# DA_Finale_Version.net
KiCad netlist of a schematic drawn in EAGLE
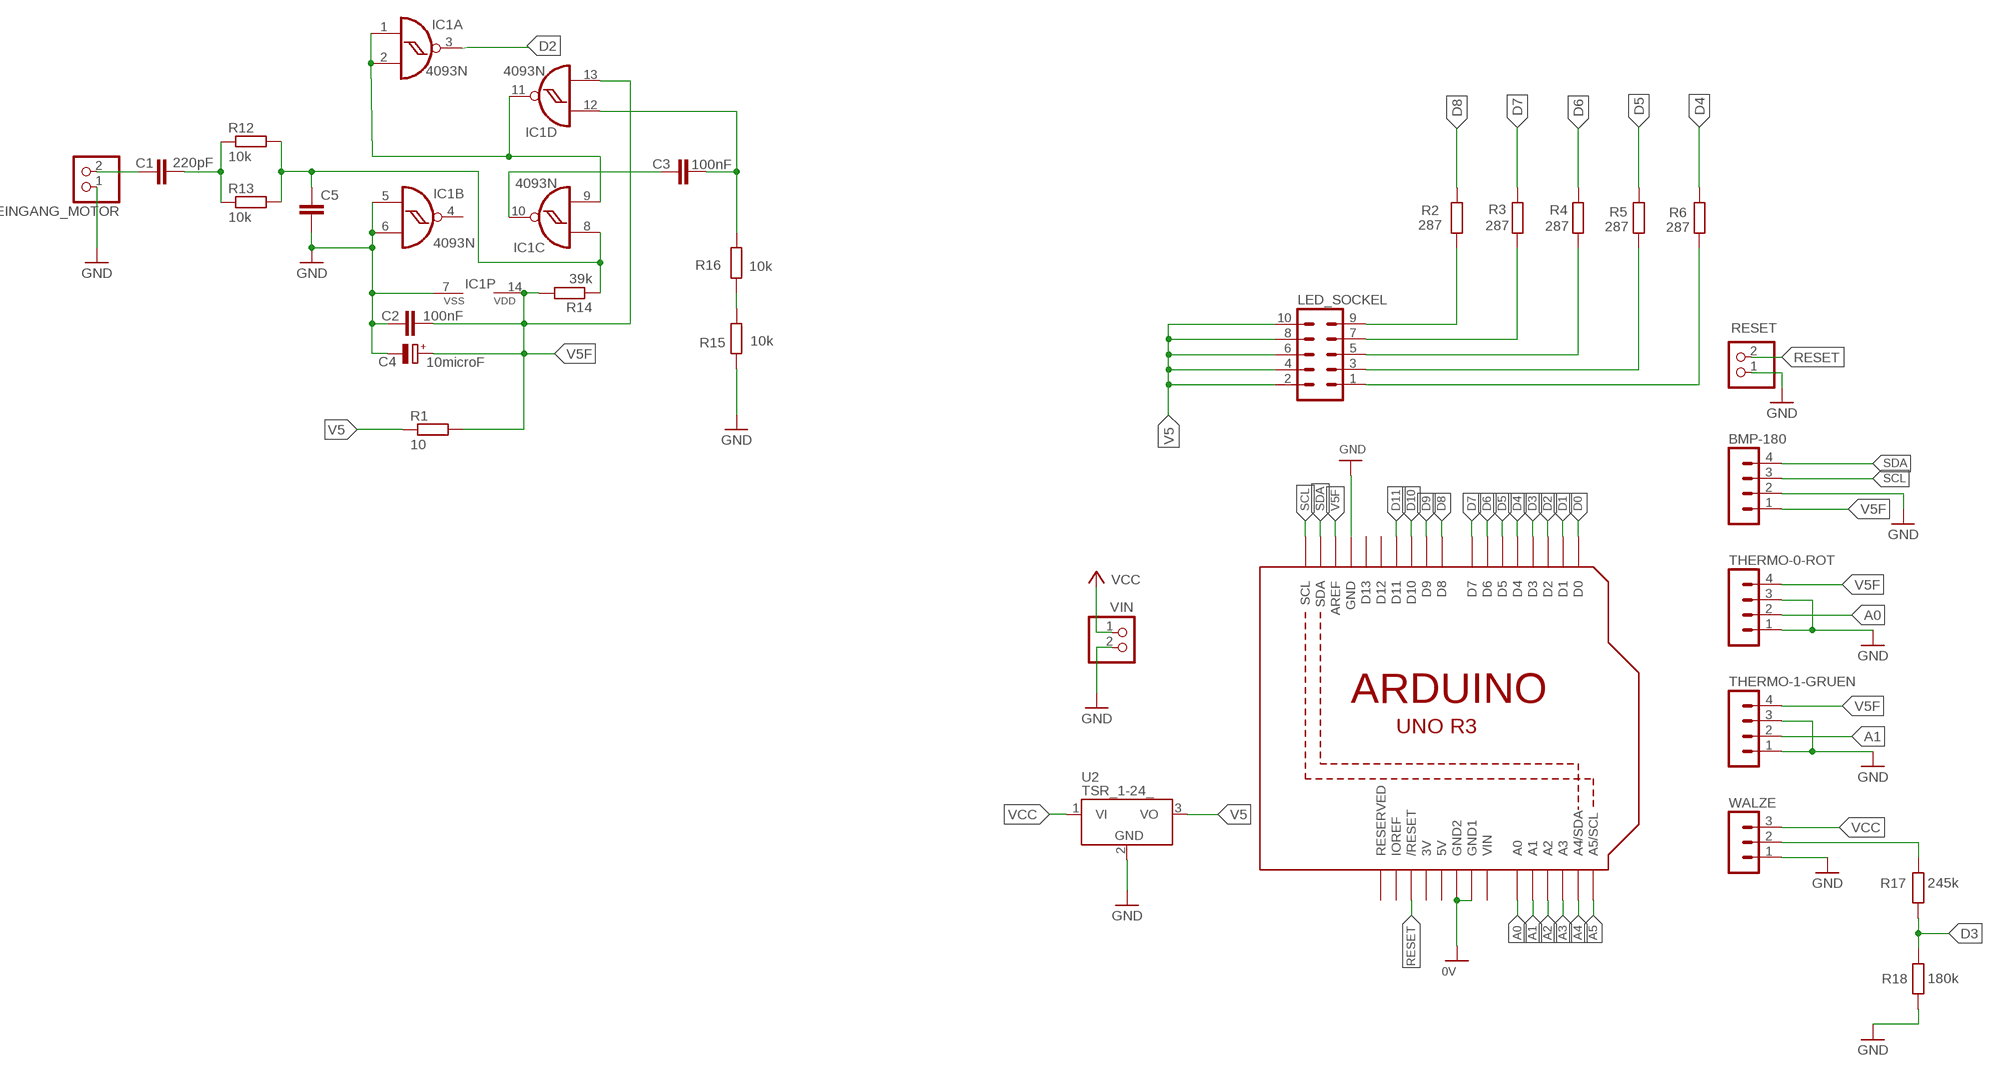
[diagram p0: schematic, sheet 1]

(export (version "E")
  (design (tool "Eeschema 10.0.6"))
  (components
    (comp (ref "BMP-180")
      (value "MA04-1")
      (footprint "eagle-import:MA04-1")
      (libsource (lib "eagle-import") (part "MA04-1"))
    )
    (comp (ref "C1")
      (value "220pF")
      (footprint "eagle-import:C050-025X075")
      (libsource (lib "eagle-import") (part "C-EU050-025X075"))
    )
    (comp (ref "C2")
      (value "100nF")
      (footprint "eagle-import:C050-025X075")
      (libsource (lib "eagle-import") (part "C-EU050-025X075"))
    )
    (comp (ref "C3")
      (value "100nF")
      (footprint "eagle-import:C050-025X075")
      (libsource (lib "eagle-import") (part "C-EU050-025X075"))
    )
    (comp (ref "C4")
      (value "10microF")
      (footprint "eagle-import:E3,5-8")
      (libsource (lib "eagle-import") (part "CPOL-EUE3.5-8"))
    )
    (comp (ref "C5")
      (value "C-EU050-025X075")
      (footprint "eagle-import:C050-025X075")
      (libsource (lib "eagle-import") (part "C-EU050-025X075"))
    )
    (comp (ref "EINGANG_MOTOR")
      (value "PINHD-1X2")
      (footprint "eagle-import:1X02")
      (libsource (lib "eagle-import") (part "PINHD-1X2"))
    )
    (comp (ref "IC1")
      (value "4093N")
      (footprint "eagle-import:DIL14")
      (libsource (lib "eagle-import") (part "4093N"))
    )
    (comp (ref "LED_SOCKEL")
      (value "MA05-2")
      (footprint "eagle-import:MA05-2")
      (libsource (lib "eagle-import") (part "MA05-2"))
    )
    (comp (ref "R1")
      (value "10")
      (footprint "eagle-import:0207_7")
      (libsource (lib "eagle-import") (part "R-EU_0207/7"))
    )
    (comp (ref "R2")
      (value "287")
      (footprint "eagle-import:0207_10")
      (libsource (lib "eagle-import") (part "R-EU_0207/10"))
    )
    (comp (ref "R3")
      (value "287")
      (footprint "eagle-import:0207_10")
      (libsource (lib "eagle-import") (part "R-EU_0207/10"))
    )
    (comp (ref "R4")
      (value "287")
      (footprint "eagle-import:0207_10")
      (libsource (lib "eagle-import") (part "R-EU_0207/10"))
    )
    (comp (ref "R5")
      (value "287")
      (footprint "eagle-import:0207_10")
      (libsource (lib "eagle-import") (part "R-EU_0207/10"))
    )
    (comp (ref "R6")
      (value "287")
      (footprint "eagle-import:0207_10")
      (libsource (lib "eagle-import") (part "R-EU_0207/10"))
    )
    (comp (ref "R12")
      (value "10k")
      (footprint "eagle-import:0207_7")
      (libsource (lib "eagle-import") (part "resistor_348_R-EU_0207/7"))
    )
    (comp (ref "R13")
      (value "10k")
      (footprint "eagle-import:0207_7")
      (libsource (lib "eagle-import") (part "resistor_348_R-EU_0207/7"))
    )
    (comp (ref "R14")
      (value "39k")
      (footprint "eagle-import:0207_7")
      (libsource (lib "eagle-import") (part "resistor_348_R-EU_0207/7"))
    )
    (comp (ref "R15")
      (value "10k")
      (footprint "eagle-import:0207_7")
      (libsource (lib "eagle-import") (part "resistor_348_R-EU_0207/7"))
    )
    (comp (ref "R16")
      (value "10k")
      (footprint "eagle-import:0207_7")
      (libsource (lib "eagle-import") (part "resistor_348_R-EU_0207/7"))
    )
    (comp (ref "R17")
      (value "245k")
      (footprint "eagle-import:0207_7")
      (libsource (lib "eagle-import") (part "resistor_348_R-EU_0207/7"))
    )
    (comp (ref "R18")
      (value "180k")
      (footprint "eagle-import:0207_7")
      (libsource (lib "eagle-import") (part "resistor_348_R-EU_0207/7"))
    )
    (comp (ref "RESET")
      (value "PINHD-1X2")
      (footprint "eagle-import:1X02")
      (libsource (lib "eagle-import") (part "PINHD-1X2"))
    )
    (comp (ref "THERMO-0-ROT")
      (value "MA04-1")
      (footprint "eagle-import:MA04-1")
      (libsource (lib "eagle-import") (part "MA04-1"))
    )
    (comp (ref "THERMO-1-GRUEN")
      (value "MA04-1")
      (footprint "eagle-import:MA04-1")
      (libsource (lib "eagle-import") (part "MA04-1"))
    )
    (comp (ref "U1")
      (value "ARDUINOR3-BPLACE")
      (footprint "eagle-import:ARDUINOR3-BPLACE")
      (libsource (lib "eagle-import") (part "ARDUINOR3-BPLACE"))
    )
    (comp (ref "U2")
      (value "TSR_1-24_")
      (footprint "eagle-import:TSR-1")
      (libsource (lib "eagle-import") (part "TSR_1-24_"))
    )
    (comp (ref "VIN")
      (value "PINHD-1X2")
      (footprint "eagle-import:1X02")
      (libsource (lib "eagle-import") (part "PINHD-1X2"))
    )
    (comp (ref "WALZE")
      (value "MA03-1")
      (footprint "eagle-import:MA03-1")
      (libsource (lib "eagle-import") (part "MA03-1"))
    )
  )
  (nets
    (net (code "1") (name "/3V") (class "Default")
      (node (ref "U1") (pin "3V") (pinfunction "3V_3V") (pintype "power_in"))
    )
    (net (code "2") (name "/5V") (class "Default")
      (node (ref "U1") (pin "5V") (pinfunction "5V_5V") (pintype "power_in"))
    )
    (net (code "3") (name "/VIN") (class "Default")
      (node (ref "U1") (pin "VIN") (pinfunction "VIN_VIN") (pintype "power_in"))
    )
    (net (code "4") (name "0V") (class "Default")
      (node (ref "BMP-180") (pin "2") (pinfunction "2_2") (pintype "passive"))
      (node (ref "C2") (pin "1") (pinfunction "1_1") (pintype "passive"))
      (node (ref "C4") (pin "-") (pinfunction "-_-") (pintype "passive"))
      (node (ref "C5") (pin "2") (pinfunction "2_2") (pintype "passive"))
      (node (ref "EINGANG_MOTOR") (pin "1") (pinfunction "1_1") (pintype "passive"))
      (node (ref "IC1") (pin "5") (pinfunction "I0_5") (pintype "input"))
      (node (ref "IC1") (pin "6") (pinfunction "I1_6") (pintype "input"))
      (node (ref "IC1") (pin "7") (pinfunction "VSS_7") (pintype "power_in"))
      (node (ref "R15") (pin "1") (pinfunction "1_1") (pintype "passive"))
      (node (ref "R18") (pin "1") (pinfunction "1_1") (pintype "passive"))
      (node (ref "RESET") (pin "1") (pinfunction "1_1") (pintype "passive"))
      (node (ref "THERMO-0-ROT") (pin "1") (pinfunction "1_1") (pintype "passive"))
      (node (ref "THERMO-0-ROT") (pin "3") (pinfunction "3_3") (pintype "passive"))
      (node (ref "THERMO-1-GRUEN") (pin "1") (pinfunction "1_1") (pintype "passive"))
      (node (ref "THERMO-1-GRUEN") (pin "3") (pinfunction "3_3") (pintype "passive"))
      (node (ref "U1") (pin "GND") (pinfunction "GND_GND") (pintype "power_in"))
      (node (ref "U1") (pin "GND1") (pinfunction "GND1_GND1") (pintype "power_in"))
      (node (ref "U1") (pin "GND2") (pinfunction "GND2_GND2") (pintype "power_in"))
      (node (ref "U2") (pin "2") (pinfunction "GND_2") (pintype "power_in"))
      (node (ref "VIN") (pin "2") (pinfunction "2_2") (pintype "passive"))
      (node (ref "WALZE") (pin "1") (pinfunction "1_1") (pintype "passive"))
    )
    (net (code "5") (name "A0") (class "Default")
      (node (ref "THERMO-0-ROT") (pin "2") (pinfunction "2_2") (pintype "passive"))
      (node (ref "U1") (pin "A0") (pinfunction "A0_A0") (pintype "bidirectional"))
    )
    (net (code "6") (name "A1") (class "Default")
      (node (ref "THERMO-1-GRUEN") (pin "2") (pinfunction "2_2") (pintype "passive"))
      (node (ref "U1") (pin "A1") (pinfunction "A1_A1") (pintype "bidirectional"))
    )
    (net (code "7") (name "A2") (class "Default")
      (node (ref "U1") (pin "A2") (pinfunction "A2_A2") (pintype "bidirectional"))
    )
    (net (code "8") (name "A3") (class "Default")
      (node (ref "U1") (pin "A3") (pinfunction "A3_A3") (pintype "bidirectional"))
    )
    (net (code "9") (name "A4") (class "Default")
      (node (ref "U1") (pin "A4") (pinfunction "A4/SDA_A4") (pintype "bidirectional"))
    )
    (net (code "10") (name "A5") (class "Default")
      (node (ref "U1") (pin "A5") (pinfunction "A5/SCL_A5") (pintype "bidirectional"))
    )
    (net (code "11") (name "D0") (class "Default")
      (node (ref "U1") (pin "D0") (pinfunction "D0_D0") (pintype "bidirectional"))
    )
    (net (code "12") (name "D1") (class "Default")
      (node (ref "U1") (pin "D1") (pinfunction "D1_D1") (pintype "bidirectional"))
    )
    (net (code "13") (name "D2") (class "Default")
      (node (ref "IC1") (pin "3") (pinfunction "O_3") (pintype "output"))
      (node (ref "U1") (pin "D2") (pinfunction "D2_D2") (pintype "bidirectional"))
    )
    (net (code "14") (name "D3") (class "Default")
      (node (ref "R17") (pin "1") (pinfunction "1_1") (pintype "passive"))
      (node (ref "R18") (pin "2") (pinfunction "2_2") (pintype "passive"))
      (node (ref "U1") (pin "D3") (pinfunction "D3_D3") (pintype "bidirectional"))
    )
    (net (code "15") (name "D4") (class "Default")
      (node (ref "R6") (pin "2") (pinfunction "2_2") (pintype "passive"))
      (node (ref "U1") (pin "D4") (pinfunction "D4_D4") (pintype "bidirectional"))
    )
    (net (code "16") (name "D5") (class "Default")
      (node (ref "R5") (pin "2") (pinfunction "2_2") (pintype "passive"))
      (node (ref "U1") (pin "D5") (pinfunction "D5_D5") (pintype "bidirectional"))
    )
    (net (code "17") (name "D6") (class "Default")
      (node (ref "R4") (pin "2") (pinfunction "2_2") (pintype "passive"))
      (node (ref "U1") (pin "D6") (pinfunction "D6_D6") (pintype "bidirectional"))
    )
    (net (code "18") (name "D7") (class "Default")
      (node (ref "R3") (pin "2") (pinfunction "2_2") (pintype "passive"))
      (node (ref "U1") (pin "D7") (pinfunction "D7_D7") (pintype "bidirectional"))
    )
    (net (code "19") (name "D8") (class "Default")
      (node (ref "R2") (pin "2") (pinfunction "2_2") (pintype "passive"))
      (node (ref "U1") (pin "D8") (pinfunction "D8_D8") (pintype "bidirectional"))
    )
    (net (code "20") (name "D9") (class "Default")
      (node (ref "U1") (pin "D9") (pinfunction "D9_D9") (pintype "bidirectional"))
    )
    (net (code "21") (name "D10") (class "Default")
      (node (ref "U1") (pin "D10") (pinfunction "D10_D10") (pintype "bidirectional"))
    )
    (net (code "22") (name "D11") (class "Default")
      (node (ref "U1") (pin "D11") (pinfunction "D11_D11") (pintype "bidirectional"))
    )
    (net (code "23") (name "Net-(C1-Pad1)") (class "Default")
      (node (ref "C1") (pin "1") (pinfunction "1_1") (pintype "passive"))
      (node (ref "EINGANG_MOTOR") (pin "2") (pinfunction "2_2") (pintype "passive"))
    )
    (net (code "24") (name "Net-(C1-Pad2)") (class "Default")
      (node (ref "C1") (pin "2") (pinfunction "2_2") (pintype "passive"))
      (node (ref "R12") (pin "1") (pinfunction "1_1") (pintype "passive"))
      (node (ref "R13") (pin "1") (pinfunction "1_1") (pintype "passive"))
    )
    (net (code "25") (name "Net-(IC1A-I0)") (class "Default")
      (node (ref "IC1") (pin "1") (pinfunction "I0_1") (pintype "input"))
      (node (ref "IC1") (pin "11") (pinfunction "O_11") (pintype "output"))
      (node (ref "IC1") (pin "2") (pinfunction "I1_2") (pintype "input"))
      (node (ref "IC1") (pin "9") (pinfunction "I1_9") (pintype "input"))
    )
    (net (code "26") (name "Net-(IC1C-I0)") (class "Default")
      (node (ref "C5") (pin "1") (pinfunction "1_1") (pintype "passive"))
      (node (ref "IC1") (pin "8") (pinfunction "I0_8") (pintype "input"))
      (node (ref "R12") (pin "2") (pinfunction "2_2") (pintype "passive"))
      (node (ref "R13") (pin "2") (pinfunction "2_2") (pintype "passive"))
      (node (ref "R14") (pin "1") (pinfunction "1_1") (pintype "passive"))
    )
    (net (code "27") (name "Net-(IC1C-O)") (class "Default")
      (node (ref "C3") (pin "2") (pinfunction "2_2") (pintype "passive"))
      (node (ref "IC1") (pin "10") (pinfunction "O_10") (pintype "output"))
    )
    (net (code "28") (name "Net-(IC1D-I0)") (class "Default")
      (node (ref "C3") (pin "1") (pinfunction "1_1") (pintype "passive"))
      (node (ref "IC1") (pin "12") (pinfunction "I0_12") (pintype "input"))
      (node (ref "R16") (pin "2") (pinfunction "2_2") (pintype "passive"))
    )
    (net (code "29") (name "Net-(LED_SOCKEL-Pad1)") (class "Default")
      (node (ref "LED_SOCKEL") (pin "1") (pinfunction "1_1") (pintype "passive"))
      (node (ref "R6") (pin "1") (pinfunction "1_1") (pintype "passive"))
    )
    (net (code "30") (name "Net-(LED_SOCKEL-Pad3)") (class "Default")
      (node (ref "LED_SOCKEL") (pin "3") (pinfunction "3_3") (pintype "passive"))
      (node (ref "R5") (pin "1") (pinfunction "1_1") (pintype "passive"))
    )
    (net (code "31") (name "Net-(LED_SOCKEL-Pad5)") (class "Default")
      (node (ref "LED_SOCKEL") (pin "5") (pinfunction "5_5") (pintype "passive"))
      (node (ref "R4") (pin "1") (pinfunction "1_1") (pintype "passive"))
    )
    (net (code "32") (name "Net-(LED_SOCKEL-Pad7)") (class "Default")
      (node (ref "LED_SOCKEL") (pin "7") (pinfunction "7_7") (pintype "passive"))
      (node (ref "R3") (pin "1") (pinfunction "1_1") (pintype "passive"))
    )
    (net (code "33") (name "Net-(LED_SOCKEL-Pad9)") (class "Default")
      (node (ref "LED_SOCKEL") (pin "9") (pinfunction "9_9") (pintype "passive"))
      (node (ref "R2") (pin "1") (pinfunction "1_1") (pintype "passive"))
    )
    (net (code "34") (name "Net-(R15-Pad2)") (class "Default")
      (node (ref "R15") (pin "2") (pinfunction "2_2") (pintype "passive"))
      (node (ref "R16") (pin "1") (pinfunction "1_1") (pintype "passive"))
    )
    (net (code "35") (name "Net-(R17-Pad2)") (class "Default")
      (node (ref "R17") (pin "2") (pinfunction "2_2") (pintype "passive"))
      (node (ref "WALZE") (pin "2") (pinfunction "2_2") (pintype "passive"))
    )
    (net (code "36") (name "RESET") (class "Default")
      (node (ref "RESET") (pin "2") (pinfunction "2_2") (pintype "passive"))
      (node (ref "U1") (pin "RESET") (pinfunction "/RESET_RESET") (pintype "bidirectional"))
    )
    (net (code "37") (name "SCL") (class "Default")
      (node (ref "BMP-180") (pin "3") (pinfunction "3_3") (pintype "passive"))
      (node (ref "U1") (pin "SCL") (pinfunction "SCL_SCL") (pintype "bidirectional"))
    )
    (net (code "38") (name "SDA") (class "Default")
      (node (ref "BMP-180") (pin "4") (pinfunction "4_4") (pintype "passive"))
      (node (ref "U1") (pin "SDA") (pinfunction "SDA_SDA") (pintype "bidirectional"))
    )
    (net (code "39") (name "V5") (class "Default")
      (node (ref "LED_SOCKEL") (pin "10") (pinfunction "10_10") (pintype "passive"))
      (node (ref "LED_SOCKEL") (pin "2") (pinfunction "2_2") (pintype "passive"))
      (node (ref "LED_SOCKEL") (pin "4") (pinfunction "4_4") (pintype "passive"))
      (node (ref "LED_SOCKEL") (pin "6") (pinfunction "6_6") (pintype "passive"))
      (node (ref "LED_SOCKEL") (pin "8") (pinfunction "8_8") (pintype "passive"))
      (node (ref "R1") (pin "1") (pinfunction "1_1") (pintype "passive"))
      (node (ref "U2") (pin "3") (pinfunction "VO_3") (pintype "power_in"))
    )
    (net (code "40") (name "V5F") (class "Default")
      (node (ref "BMP-180") (pin "1") (pinfunction "1_1") (pintype "passive"))
      (node (ref "C2") (pin "2") (pinfunction "2_2") (pintype "passive"))
      (node (ref "C4") (pin "+") (pinfunction "+_+") (pintype "passive"))
      (node (ref "IC1") (pin "13") (pinfunction "I1_13") (pintype "input"))
      (node (ref "IC1") (pin "14") (pinfunction "VDD_14") (pintype "power_in"))
      (node (ref "R1") (pin "2") (pinfunction "2_2") (pintype "passive"))
      (node (ref "R14") (pin "2") (pinfunction "2_2") (pintype "passive"))
      (node (ref "THERMO-0-ROT") (pin "4") (pinfunction "4_4") (pintype "passive"))
      (node (ref "THERMO-1-GRUEN") (pin "4") (pinfunction "4_4") (pintype "passive"))
      (node (ref "U1") (pin "AREF") (pinfunction "AREF_AREF") (pintype "bidirectional"))
    )
    (net (code "41") (name "VCC") (class "Default")
      (node (ref "U2") (pin "1") (pinfunction "VI_1") (pintype "power_in"))
      (node (ref "VIN") (pin "1") (pinfunction "1_1") (pintype "passive"))
      (node (ref "WALZE") (pin "3") (pinfunction "3_3") (pintype "passive"))
    )
    (net (code "42") (name "unconnected-(IC1B-O-Pad4)") (class "Default")
      (node (ref "IC1") (pin "4") (pinfunction "O_4") (pintype "output"))
    )
    (net (code "43") (name "unconnected-(U1-PadD12)") (class "Default")
      (node (ref "U1") (pin "D12") (pinfunction "D12_D12") (pintype "bidirectional"))
    )
    (net (code "44") (name "unconnected-(U1-PadD13)") (class "Default")
      (node (ref "U1") (pin "D13") (pinfunction "D13_D13") (pintype "bidirectional"))
    )
    (net (code "45") (name "unconnected-(U1-PadIOREF)") (class "Default")
      (node (ref "U1") (pin "IOREF") (pinfunction "IOREF_IOREF") (pintype "output"))
    )
    (net (code "46") (name "unconnected-(U1-PadRESERVED)") (class "Default")
      (node (ref "U1") (pin "RESERVED") (pinfunction "RESERVED_RESERVED") (pintype "no_connect"))
    )
  )
)
